# PWR.net
KiCad netlist of a schematic drawn in EAGLE
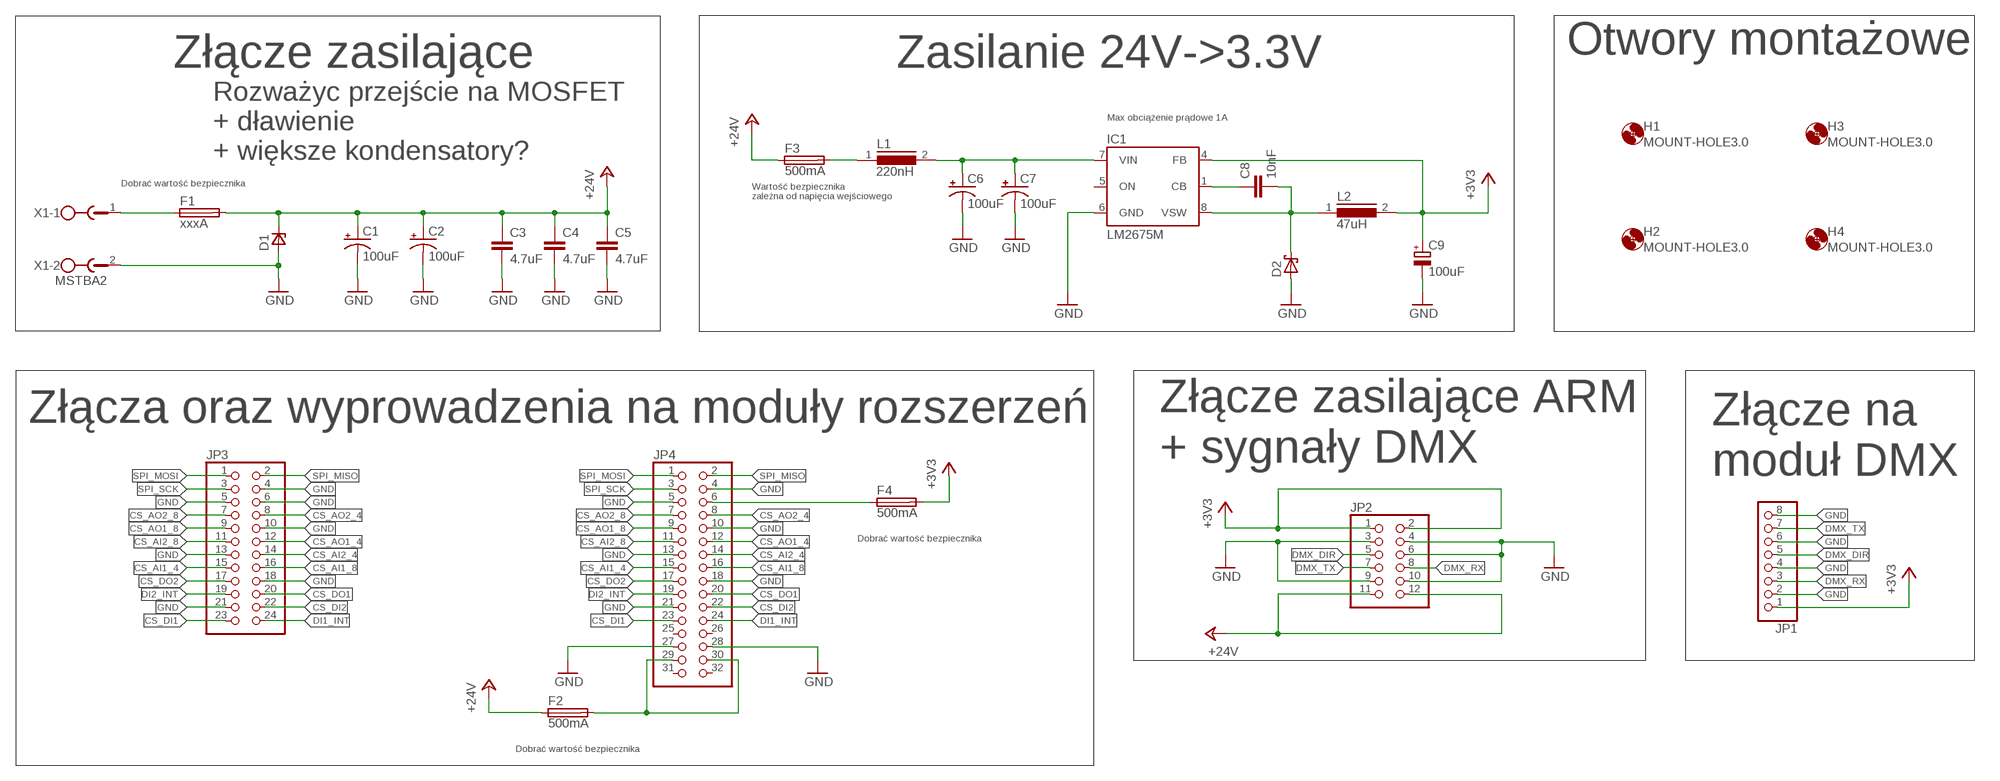
[diagram p0: schematic, sheet 1]

(export (version "E")
  (design (tool "Eeschema 10.0.6"))
  (components
    (comp (ref "C1")
      (value "100uF")
      (footprint "eagle-import:TT5D10")
      (fields (field (name "MF") "Nichicon") (field (name "MPN") "UPJ1H101MPD6"))
      (libsource (lib "eagle-import") (part "CPOL-USTT5D10"))
    )
    (comp (ref "C2")
      (value "100uF")
      (footprint "eagle-import:TT5D10")
      (fields (field (name "MF") "Nichicon") (field (name "MPN") "UPJ1H101MPD6"))
      (libsource (lib "eagle-import") (part "CPOL-USTT5D10"))
    )
    (comp (ref "C3")
      (value "4.7uF")
      (footprint "eagle-import:C0805")
      (fields (field (name "MF") "Murata Electronics") (field (name "MPN") "GRM21BR61H475ME51L"))
      (libsource (lib "eagle-import") (part "C-EUC0805"))
    )
    (comp (ref "C4")
      (value "4.7uF")
      (footprint "eagle-import:C0805")
      (fields (field (name "MF") "Murata Electronics") (field (name "MPN") "GRM21BR61H475ME51L"))
      (libsource (lib "eagle-import") (part "C-EUC0805"))
    )
    (comp (ref "C5")
      (value "4.7uF")
      (footprint "eagle-import:C0805")
      (fields (field (name "MF") "Murata Electronics") (field (name "MPN") "GRM21BR61H475ME51L"))
      (libsource (lib "eagle-import") (part "C-EUC0805"))
    )
    (comp (ref "C6")
      (value "100uF")
      (footprint "eagle-import:TT5D10")
      (fields (field (name "MF") "Nichicon") (field (name "MPN") "UPJ1H101MPD6"))
      (libsource (lib "eagle-import") (part "CPOL-USTT5D10"))
    )
    (comp (ref "C7")
      (value "100uF")
      (footprint "eagle-import:TT5D10")
      (fields (field (name "MF") "Nichicon") (field (name "MPN") "UPJ1H101MPD6"))
      (libsource (lib "eagle-import") (part "CPOL-USTT5D10"))
    )
    (comp (ref "C8")
      (value "10nF")
      (footprint "eagle-import:C0603")
      (fields (field (name "MF") "AVX") (field (name "MPN") "06035C103KAT2A"))
      (libsource (lib "eagle-import") (part "C-EUC0603"))
    )
    (comp (ref "C9")
      (value "100uF")
      (footprint "eagle-import:SMC_C")
      (fields (field (name "MF") "AVX") (field (name "MPN") "TAJC107K010TNJ"))
      (libsource (lib "eagle-import") (part "CPOL-EUSMCC"))
    )
    (comp (ref "D1")
      (value "P6SMB20A")
      (footprint "eagle-import:SMB_A")
      (fields (field (name "MF") "Littelfuse") (field (name "MPN") "TPSMB24A-VR"))
      (libsource (lib "eagle-import") (part "P6SMBA20"))
    )
    (comp (ref "D2")
      (value "SCHOTTKY-DIODESMD")
      (footprint "eagle-import:SMB")
      (fields (field (name "MF") "ON Semiconductor") (field (name "MPN") "SS26T3G"))
      (libsource (lib "eagle-import") (part "SCHOTTKY-DIODESMD"))
    )
    (comp (ref "F1")
      (value "xxxA")
      (footprint "eagle-import:TR5")
      (fields (field (name "MF") "Littelfuse") (field (name "MPN") "56000001009"))
      (libsource (lib "eagle-import") (part "TR5"))
    )
    (comp (ref "F2")
      (value "500mA")
      (footprint "eagle-import:TR5")
      (fields (field (name "MF") "Littelfuse") (field (name "MPN") "56000001009"))
      (libsource (lib "eagle-import") (part "TR5"))
    )
    (comp (ref "F3")
      (value "500mA")
      (footprint "eagle-import:TR5")
      (fields (field (name "MF") "Littelfuse") (field (name "MPN") "56000001009"))
      (libsource (lib "eagle-import") (part "TR5"))
    )
    (comp (ref "F4")
      (value "500mA")
      (footprint "eagle-import:TR5")
      (fields (field (name "MF") "Littelfuse") (field (name "MPN") "56000001009"))
      (libsource (lib "eagle-import") (part "TR5"))
    )
    (comp (ref "H1")
      (value "MOUNT-HOLE3.0")
      (footprint "eagle-import:3,0")
      (libsource (lib "eagle-import") (part "MOUNT-HOLE3.0"))
    )
    (comp (ref "H2")
      (value "MOUNT-HOLE3.0")
      (footprint "eagle-import:3,0")
      (libsource (lib "eagle-import") (part "MOUNT-HOLE3.0"))
    )
    (comp (ref "H3")
      (value "MOUNT-HOLE3.0")
      (footprint "eagle-import:3,0")
      (libsource (lib "eagle-import") (part "MOUNT-HOLE3.0"))
    )
    (comp (ref "H4")
      (value "MOUNT-HOLE3.0")
      (footprint "eagle-import:3,0")
      (libsource (lib "eagle-import") (part "MOUNT-HOLE3.0"))
    )
    (comp (ref "IC1")
      (value "LM2675M")
      (footprint "eagle-import:SO08")
      (fields (field (name "MF") "Texas Instruments") (field (name "MPN") "LM2675MX-3.3/NOPB"))
      (libsource (lib "eagle-import") (part "LM2675M"))
    )
    (comp (ref "JP1")
      (value "PINHD-1X8/90")
      (footprint "eagle-import:1X08_90")
      (fields (field (name "MF") "CONNFLY") (field (name "MPN") "DS1024-1*8R0"))
      (libsource (lib "eagle-import") (part "PINHD-1X8/90"))
    )
    (comp (ref "JP2")
      (value "PINHD-2X6")
      (footprint "eagle-import:2X06")
      (fields (field (name "MF") "CONNFLY") (field (name "MPN") "DS1023-2*6S21"))
      (libsource (lib "eagle-import") (part "PINHD-2X6"))
    )
    (comp (ref "JP3")
      (value "PINHD-2X12")
      (footprint "eagle-import:2X12")
      (fields (field (name "MF") "CONNFLY") (field (name "MPN") "DS1023-2*12S21"))
      (libsource (lib "eagle-import") (part "PINHD-2X12"))
    )
    (comp (ref "JP4")
      (value "PINHD-2X16/90")
      (footprint "eagle-import:2X16_90")
      (fields (field (name "MF") "CONNFLY") (field (name "MPN") "DS1024-2*16R0"))
      (libsource (lib "eagle-import") (part "PINHD-2X16/90"))
    )
    (comp (ref "L1")
      (value "220nH")
      (footprint "eagle-import:7.3X6.3")
      (fields (field (name "MF") "Bourns") (field (name "MPN") "SRP7028A-R22Y"))
      (libsource (lib "eagle-import") (part "SRP7028A-R33M"))
    )
    (comp (ref "L2")
      (value "47uH")
      (footprint "eagle-import:12.5X12.5")
      (fields (field (name "MF") "Bourns") (field (name "MPN") "SRR1280-470M"))
      (libsource (lib "eagle-import") (part "SRR1280-101M"))
    )
    (comp (ref "X1")
      (value "MSTBA2")
      (footprint "eagle-import:MSTBA2")
      (fields
        (field (name "MF") "FARNELL")
        (field (name "MPN") "1757242")
        (field (name "MF_1") "DEGSON ELECTRONICS")
        (field (name "MPN_1") "2EDGRC-5.08-02P-14-00A(H)")
      )
      (libsource (lib "eagle-import") (part "MSTBA2"))
    )
  )
  (nets
    (net (code "1") (name "+3V3") (class "Default")
      (node (ref "C9") (pin "+") (pinfunction "+_+") (pintype "passive"))
      (node (ref "F4") (pin "2") (pinfunction "2_2") (pintype "passive"))
      (node (ref "IC1") (pin "4") (pinfunction "FB_4") (pintype "input"))
      (node (ref "JP1") (pin "1") (pinfunction "1_1") (pintype "passive"))
      (node (ref "JP2") (pin "1") (pinfunction "1_1") (pintype "passive"))
      (node (ref "JP2") (pin "2") (pinfunction "2_2") (pintype "passive"))
      (node (ref "L2") (pin "2") (pinfunction "2_2") (pintype "passive"))
    )
    (net (code "2") (name "+24V") (class "Default")
      (node (ref "C1") (pin "+") (pinfunction "+_+") (pintype "passive"))
      (node (ref "C2") (pin "+") (pinfunction "+_+") (pintype "passive"))
      (node (ref "C3") (pin "1") (pinfunction "1_1") (pintype "passive"))
      (node (ref "C4") (pin "1") (pinfunction "1_1") (pintype "passive"))
      (node (ref "C5") (pin "1") (pinfunction "1_1") (pintype "passive"))
      (node (ref "D1") (pin "C") (pinfunction "C_C") (pintype "passive"))
      (node (ref "F1") (pin "2") (pinfunction "2_2") (pintype "passive"))
      (node (ref "F2") (pin "1") (pinfunction "1_1") (pintype "passive"))
      (node (ref "F3") (pin "1") (pinfunction "1_1") (pintype "passive"))
      (node (ref "JP2") (pin "11") (pinfunction "11_11") (pintype "passive"))
      (node (ref "JP2") (pin "12") (pinfunction "12_12") (pintype "passive"))
    )
    (net (code "3") (name "CS_AI1_4") (class "Default")
      (node (ref "JP3") (pin "15") (pinfunction "15_15") (pintype "passive"))
      (node (ref "JP4") (pin "15") (pinfunction "15_15") (pintype "passive"))
    )
    (net (code "4") (name "CS_AI1_8") (class "Default")
      (node (ref "JP3") (pin "16") (pinfunction "16_16") (pintype "passive"))
      (node (ref "JP4") (pin "16") (pinfunction "16_16") (pintype "passive"))
    )
    (net (code "5") (name "CS_AI2_4") (class "Default")
      (node (ref "JP3") (pin "14") (pinfunction "14_14") (pintype "passive"))
      (node (ref "JP4") (pin "14") (pinfunction "14_14") (pintype "passive"))
    )
    (net (code "6") (name "CS_AI2_8") (class "Default")
      (node (ref "JP3") (pin "11") (pinfunction "11_11") (pintype "passive"))
      (node (ref "JP4") (pin "11") (pinfunction "11_11") (pintype "passive"))
    )
    (net (code "7") (name "CS_AO1_4") (class "Default")
      (node (ref "JP3") (pin "12") (pinfunction "12_12") (pintype "passive"))
      (node (ref "JP4") (pin "12") (pinfunction "12_12") (pintype "passive"))
    )
    (net (code "8") (name "CS_AO1_8") (class "Default")
      (node (ref "JP3") (pin "9") (pinfunction "9_9") (pintype "passive"))
      (node (ref "JP4") (pin "9") (pinfunction "9_9") (pintype "passive"))
    )
    (net (code "9") (name "CS_AO2_4") (class "Default")
      (node (ref "JP3") (pin "8") (pinfunction "8_8") (pintype "passive"))
      (node (ref "JP4") (pin "8") (pinfunction "8_8") (pintype "passive"))
    )
    (net (code "10") (name "CS_AO2_8") (class "Default")
      (node (ref "JP3") (pin "7") (pinfunction "7_7") (pintype "passive"))
      (node (ref "JP4") (pin "7") (pinfunction "7_7") (pintype "passive"))
    )
    (net (code "11") (name "CS_DI1") (class "Default")
      (node (ref "JP3") (pin "23") (pinfunction "23_23") (pintype "passive"))
      (node (ref "JP4") (pin "23") (pinfunction "23_23") (pintype "passive"))
    )
    (net (code "12") (name "CS_DI2") (class "Default")
      (node (ref "JP3") (pin "22") (pinfunction "22_22") (pintype "passive"))
      (node (ref "JP4") (pin "22") (pinfunction "22_22") (pintype "passive"))
    )
    (net (code "13") (name "CS_DO1") (class "Default")
      (node (ref "JP3") (pin "20") (pinfunction "20_20") (pintype "passive"))
      (node (ref "JP4") (pin "20") (pinfunction "20_20") (pintype "passive"))
    )
    (net (code "14") (name "CS_DO2") (class "Default")
      (node (ref "JP3") (pin "17") (pinfunction "17_17") (pintype "passive"))
      (node (ref "JP4") (pin "17") (pinfunction "17_17") (pintype "passive"))
    )
    (net (code "15") (name "DI1_INT") (class "Default")
      (node (ref "JP3") (pin "24") (pinfunction "24_24") (pintype "passive"))
      (node (ref "JP4") (pin "24") (pinfunction "24_24") (pintype "passive"))
    )
    (net (code "16") (name "DI2_INT") (class "Default")
      (node (ref "JP3") (pin "19") (pinfunction "19_19") (pintype "passive"))
      (node (ref "JP4") (pin "19") (pinfunction "19_19") (pintype "passive"))
    )
    (net (code "17") (name "DMX_DIR") (class "Default")
      (node (ref "JP1") (pin "5") (pinfunction "5_5") (pintype "passive"))
      (node (ref "JP2") (pin "5") (pinfunction "5_5") (pintype "passive"))
    )
    (net (code "18") (name "DMX_RX") (class "Default")
      (node (ref "JP1") (pin "3") (pinfunction "3_3") (pintype "passive"))
      (node (ref "JP2") (pin "8") (pinfunction "8_8") (pintype "passive"))
    )
    (net (code "19") (name "DMX_TX") (class "Default")
      (node (ref "JP1") (pin "7") (pinfunction "7_7") (pintype "passive"))
      (node (ref "JP2") (pin "7") (pinfunction "7_7") (pintype "passive"))
    )
    (net (code "20") (name "GND") (class "Default")
      (node (ref "C1") (pin "-") (pinfunction "-_-") (pintype "passive"))
      (node (ref "C2") (pin "-") (pinfunction "-_-") (pintype "passive"))
      (node (ref "C3") (pin "2") (pinfunction "2_2") (pintype "passive"))
      (node (ref "C4") (pin "2") (pinfunction "2_2") (pintype "passive"))
      (node (ref "C5") (pin "2") (pinfunction "2_2") (pintype "passive"))
      (node (ref "C6") (pin "-") (pinfunction "-_-") (pintype "passive"))
      (node (ref "C7") (pin "-") (pinfunction "-_-") (pintype "passive"))
      (node (ref "C9") (pin "-") (pinfunction "-_-") (pintype "passive"))
      (node (ref "D1") (pin "A") (pinfunction "A_A") (pintype "passive"))
      (node (ref "D2") (pin "A") (pinfunction "A_A") (pintype "passive"))
      (node (ref "IC1") (pin "6") (pinfunction "GND_6") (pintype "power_in"))
      (node (ref "JP1") (pin "2") (pinfunction "2_2") (pintype "passive"))
      (node (ref "JP1") (pin "4") (pinfunction "4_4") (pintype "passive"))
      (node (ref "JP1") (pin "6") (pinfunction "6_6") (pintype "passive"))
      (node (ref "JP1") (pin "8") (pinfunction "8_8") (pintype "passive"))
      (node (ref "JP2") (pin "10") (pinfunction "10_10") (pintype "passive"))
      (node (ref "JP2") (pin "3") (pinfunction "3_3") (pintype "passive"))
      (node (ref "JP2") (pin "4") (pinfunction "4_4") (pintype "passive"))
      (node (ref "JP2") (pin "6") (pinfunction "6_6") (pintype "passive"))
      (node (ref "JP2") (pin "9") (pinfunction "9_9") (pintype "passive"))
      (node (ref "JP3") (pin "10") (pinfunction "10_10") (pintype "passive"))
      (node (ref "JP3") (pin "13") (pinfunction "13_13") (pintype "passive"))
      (node (ref "JP3") (pin "18") (pinfunction "18_18") (pintype "passive"))
      (node (ref "JP3") (pin "21") (pinfunction "21_21") (pintype "passive"))
      (node (ref "JP3") (pin "4") (pinfunction "4_4") (pintype "passive"))
      (node (ref "JP3") (pin "5") (pinfunction "5_5") (pintype "passive"))
      (node (ref "JP3") (pin "6") (pinfunction "6_6") (pintype "passive"))
      (node (ref "JP4") (pin "10") (pinfunction "10_10") (pintype "passive"))
      (node (ref "JP4") (pin "13") (pinfunction "13_13") (pintype "passive"))
      (node (ref "JP4") (pin "18") (pinfunction "18_18") (pintype "passive"))
      (node (ref "JP4") (pin "21") (pinfunction "21_21") (pintype "passive"))
      (node (ref "JP4") (pin "27") (pinfunction "27_27") (pintype "passive"))
      (node (ref "JP4") (pin "28") (pinfunction "28_28") (pintype "passive"))
      (node (ref "JP4") (pin "4") (pinfunction "4_4") (pintype "passive"))
      (node (ref "JP4") (pin "5") (pinfunction "5_5") (pintype "passive"))
      (node (ref "X1") (pin "2") (pinfunction "1_2") (pintype "passive"))
    )
    (net (code "21") (name "Net-(F1-Pad1)") (class "Default")
      (node (ref "F1") (pin "1") (pinfunction "1_1") (pintype "passive"))
      (node (ref "X1") (pin "1") (pinfunction "1_1") (pintype "passive"))
    )
    (net (code "22") (name "Net-(F2-Pad2)") (class "Default")
      (node (ref "F2") (pin "2") (pinfunction "2_2") (pintype "passive"))
      (node (ref "JP4") (pin "29") (pinfunction "29_29") (pintype "passive"))
      (node (ref "JP4") (pin "30") (pinfunction "30_30") (pintype "passive"))
    )
    (net (code "23") (name "Net-(F3-Pad2)") (class "Default")
      (node (ref "F3") (pin "2") (pinfunction "2_2") (pintype "passive"))
      (node (ref "L1") (pin "1") (pinfunction "1_1") (pintype "passive"))
    )
    (net (code "24") (name "Net-(F4-Pad1)") (class "Default")
      (node (ref "F4") (pin "1") (pinfunction "1_1") (pintype "passive"))
      (node (ref "JP4") (pin "6") (pinfunction "6_6") (pintype "passive"))
    )
    (net (code "25") (name "Net-(IC1-CB)") (class "Default")
      (node (ref "C8") (pin "1") (pinfunction "1_1") (pintype "passive"))
      (node (ref "IC1") (pin "1") (pinfunction "CB_1") (pintype "input"))
    )
    (net (code "26") (name "Net-(IC1-VIN)") (class "Default")
      (node (ref "C6") (pin "+") (pinfunction "+_+") (pintype "passive"))
      (node (ref "C7") (pin "+") (pinfunction "+_+") (pintype "passive"))
      (node (ref "IC1") (pin "7") (pinfunction "VIN_7") (pintype "power_in"))
      (node (ref "L1") (pin "2") (pinfunction "2_2") (pintype "passive"))
    )
    (net (code "27") (name "Net-(IC1-VSW)") (class "Default")
      (node (ref "C8") (pin "2") (pinfunction "2_2") (pintype "passive"))
      (node (ref "D2") (pin "C") (pinfunction "C_C") (pintype "passive"))
      (node (ref "IC1") (pin "8") (pinfunction "VSW_8") (pintype "output"))
      (node (ref "L2") (pin "1") (pinfunction "1_1") (pintype "passive"))
    )
    (net (code "28") (name "SPI_MISO") (class "Default")
      (node (ref "JP3") (pin "2") (pinfunction "2_2") (pintype "passive"))
      (node (ref "JP4") (pin "2") (pinfunction "2_2") (pintype "passive"))
    )
    (net (code "29") (name "SPI_MOSI") (class "Default")
      (node (ref "JP3") (pin "1") (pinfunction "1_1") (pintype "passive"))
      (node (ref "JP4") (pin "1") (pinfunction "1_1") (pintype "passive"))
    )
    (net (code "30") (name "SPI_SCK") (class "Default")
      (node (ref "JP3") (pin "3") (pinfunction "3_3") (pintype "passive"))
      (node (ref "JP4") (pin "3") (pinfunction "3_3") (pintype "passive"))
    )
    (net (code "31") (name "unconnected-(IC1-ON-Pad5)") (class "Default")
      (node (ref "IC1") (pin "5") (pinfunction "ON_5") (pintype "passive"))
    )
    (net (code "32") (name "unconnected-(JP4-Pad25)") (class "Default")
      (node (ref "JP4") (pin "25") (pinfunction "25_25") (pintype "passive"))
    )
    (net (code "33") (name "unconnected-(JP4-Pad26)") (class "Default")
      (node (ref "JP4") (pin "26") (pinfunction "26_26") (pintype "passive"))
    )
    (net (code "34") (name "unconnected-(JP4-Pad31)") (class "Default")
      (node (ref "JP4") (pin "31") (pinfunction "31_31") (pintype "passive"))
    )
    (net (code "35") (name "unconnected-(JP4-Pad32)") (class "Default")
      (node (ref "JP4") (pin "32") (pinfunction "32_32") (pintype "passive"))
    )
  )
)
